# transmitter.net
KiCad netlist of a schematic drawn in EAGLE
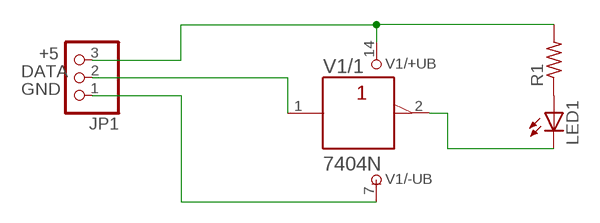
[diagram p0: schematic, sheet 1]

(export (version "E")
  (design (tool "Eeschema 10.0.6"))
  (components
    (comp (ref "JP1")
      (value "PINHD-1X3")
      (footprint "eagle-import:1X03")
      (libsource (lib "eagle-import") (part "PINHD-1X3"))
    )
    (comp (ref "LED1")
      (value "LED5MM")
      (footprint "eagle-import:LED5MM")
      (libsource (lib "eagle-import") (part "LED5MM"))
    )
    (comp (ref "R1")
      (value "R-US_0207/10")
      (footprint "eagle-import:0207_10")
      (libsource (lib "eagle-import") (part "R-US_0207/10"))
    )
    (comp (ref "V1")
      (value "7404N")
      (footprint "eagle-import:DIL14")
      (libsource (lib "eagle-import") (part "7404N"))
    )
  )
  (nets
    (net (code "1") (name "/+5") (class "Default")
      (node (ref "JP1") (pin "3") (pinfunction "3_3") (pintype "passive"))
      (node (ref "R1") (pin "2") (pinfunction "2_2") (pintype "passive"))
      (node (ref "V1") (pin "14") (pinfunction "+UB_14") (pintype "power_in"))
    )
    (net (code "2") (name "/DATA") (class "Default")
      (node (ref "JP1") (pin "2") (pinfunction "2_2") (pintype "passive"))
      (node (ref "V1") (pin "1") (pinfunction "A_1") (pintype "input"))
    )
    (net (code "3") (name "/GND") (class "Default")
      (node (ref "JP1") (pin "1") (pinfunction "1_1") (pintype "passive"))
      (node (ref "V1") (pin "7") (pinfunction "-UB_7") (pintype "power_in"))
    )
    (net (code "4") (name "Net-(LED1-C)") (class "Default")
      (node (ref "LED1") (pin "K") (pinfunction "C_K") (pintype "passive"))
      (node (ref "V1") (pin "2") (pinfunction "Y_2") (pintype "output"))
    )
    (net (code "5") (name "Net-(LED1-PadA)") (class "Default")
      (node (ref "LED1") (pin "A") (pinfunction "A_A") (pintype "passive"))
      (node (ref "R1") (pin "1") (pinfunction "1_1") (pintype "passive"))
    )
  )
)
